# 02_MCU.net
KiCad netlist of a schematic drawn in Altium Designer
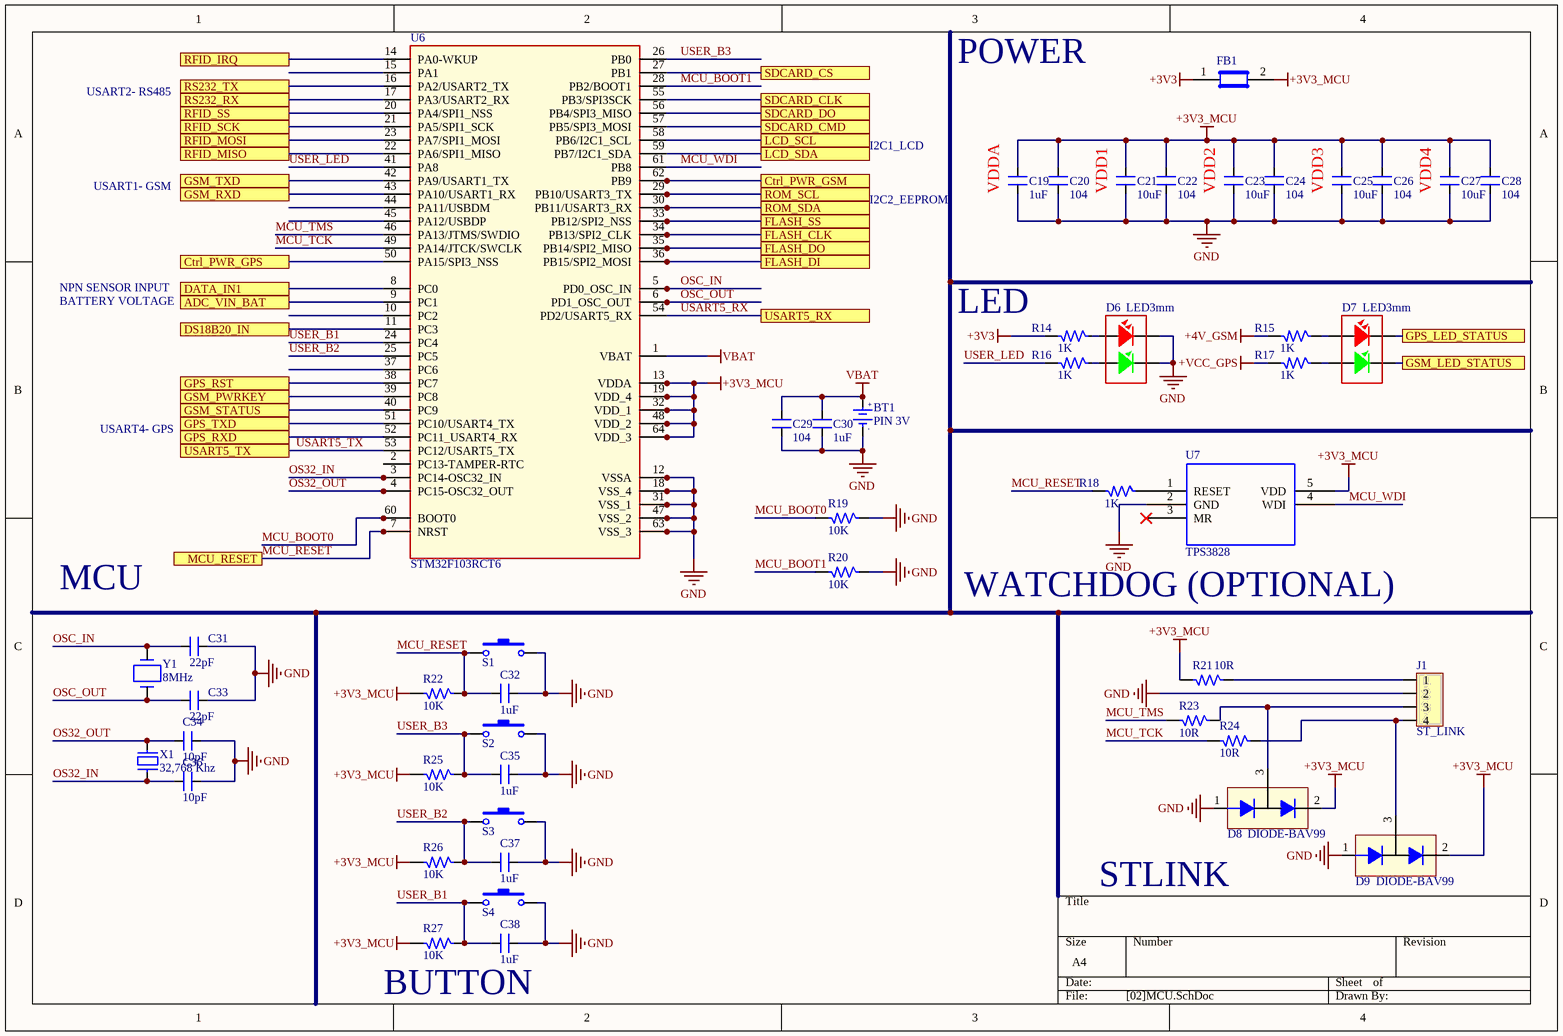
[diagram p0: [02]MCU.SchDoc]

(export (version "E")
  (design (tool "Eeschema 10.0.6"))
  (components
    (comp (ref "BT1")
      (value "PIN 3V")
      (footprint "My Library:CR1220 SMD")
      (description "Battery 3VDC")
      (libsource (lib "My Library") (part "PIN 3V"))
    )
    (comp (ref "C19")
      (value "1uF")
      (footprint "C0603 SMT")
      (description "Cap SMD")
      (libsource (lib "GPS_Traking_V1_1") (part "CM"))
    )
    (comp (ref "C20")
      (value "104")
      (footprint "C0603 SMT")
      (description "Cap SMD")
      (libsource (lib "GPS_Traking_V1_1") (part "CM"))
    )
    (comp (ref "C21")
      (value "10uF")
      (footprint "C0603 SMT")
      (description "Cap SMD")
      (libsource (lib "GPS_Traking_V1_1") (part "CM"))
    )
    (comp (ref "C22")
      (value "104")
      (footprint "C0603 SMT")
      (description "Cap SMD")
      (libsource (lib "GPS_Traking_V1_1") (part "CM"))
    )
    (comp (ref "C23")
      (value "10uF")
      (footprint "C0603 SMT")
      (description "Cap SMD")
      (libsource (lib "GPS_Traking_V1_1") (part "CM"))
    )
    (comp (ref "C24")
      (value "104")
      (footprint "C0603 SMT")
      (description "Cap SMD")
      (libsource (lib "GPS_Traking_V1_1") (part "CM"))
    )
    (comp (ref "C25")
      (value "10uF")
      (footprint "C0603 SMT")
      (description "Cap SMD")
      (libsource (lib "GPS_Traking_V1_1") (part "CM"))
    )
    (comp (ref "C26")
      (value "104")
      (footprint "C0603 SMT")
      (description "Cap SMD")
      (libsource (lib "GPS_Traking_V1_1") (part "CM"))
    )
    (comp (ref "C27")
      (value "10uF")
      (footprint "C0603 SMT")
      (description "Cap SMD")
      (libsource (lib "GPS_Traking_V1_1") (part "CM"))
    )
    (comp (ref "C28")
      (value "104")
      (footprint "C0603 SMT")
      (description "Cap SMD")
      (libsource (lib "GPS_Traking_V1_1") (part "CM"))
    )
    (comp (ref "C29")
      (value "104")
      (footprint "C0603 SMT")
      (description "Cap SMD")
      (libsource (lib "GPS_Traking_V1_1") (part "CM"))
    )
    (comp (ref "C30")
      (value "1uF")
      (footprint "C0603 SMT")
      (description "Cap SMD")
      (libsource (lib "GPS_Traking_V1_1") (part "CM"))
    )
    (comp (ref "C31")
      (value "22pF")
      (footprint "C0603 SMT")
      (description "Cap SMD")
      (libsource (lib "GPS_Traking_V1_1") (part "CM"))
    )
    (comp (ref "C32")
      (value "1uF")
      (footprint "C0603 SMT")
      (description "Cap SMD")
      (libsource (lib "GPS_Traking_V1_1") (part "CM"))
    )
    (comp (ref "C33")
      (value "22pF")
      (footprint "C0603 SMT")
      (description "Cap SMD")
      (libsource (lib "GPS_Traking_V1_1") (part "CM"))
    )
    (comp (ref "C34")
      (value "10pF")
      (footprint "C0603 SMT")
      (description "Cap SMD")
      (libsource (lib "GPS_Traking_V1_1") (part "CM"))
    )
    (comp (ref "C35")
      (value "1uF")
      (footprint "C0603 SMT")
      (description "Cap SMD")
      (libsource (lib "GPS_Traking_V1_1") (part "CM"))
    )
    (comp (ref "C36")
      (value "10pF")
      (footprint "C0603 SMT")
      (description "Cap SMD")
      (libsource (lib "GPS_Traking_V1_1") (part "CM"))
    )
    (comp (ref "C37")
      (value "1uF")
      (footprint "C0603 SMT")
      (description "Cap SMD")
      (libsource (lib "GPS_Traking_V1_1") (part "CM"))
    )
    (comp (ref "C38")
      (value "1uF")
      (footprint "C0603 SMT")
      (description "Cap SMD")
      (libsource (lib "GPS_Traking_V1_1") (part "CM"))
    )
    (comp (ref "D6")
      (value "LED3mm")
      (footprint "GPS_Traking_V1_1:LED 2 holder 3mm")
      (description "LED 2 holder RGB 3mm")
      (libsource (lib "GPS_Traking_V1_1") (part "LED2Holder_3mm"))
    )
    (comp (ref "D7")
      (value "LED3mm")
      (footprint "GPS_Traking_V1_1:LED 2 holder 3mm")
      (description "LED 2 holder RGB 3mm")
      (libsource (lib "GPS_Traking_V1_1") (part "LED2Holder_3mm"))
    )
    (comp (ref "D8")
      (value "DIODE-BAV99")
      (footprint "SOT23")
      (description "ZENER, SOT23,")
      (fields
        (field (name "MANUFACTURER") "ON Semiconductor / Fairchild")
        (field (name "MANUFACTURER PART NUMBER") "BAV99")
        (field (name ".CREATOR") "LeKhaLinh")
        (field (name ".CHECKPCB") "LeKhaLinh")
        (field (name ".CHECKSCH") "LeKhaLinh")
      )
      (libsource (lib "GPS_Traking_V1_1") (part "DIODE-BAV99"))
    )
    (comp (ref "D9")
      (value "DIODE-BAV99")
      (footprint "SOT23")
      (description "ZENER, SOT23,")
      (fields
        (field (name "MANUFACTURER") "ON Semiconductor / Fairchild")
        (field (name "MANUFACTURER PART NUMBER") "BAV99")
        (field (name ".CREATOR") "LeKhaLinh")
        (field (name ".CHECKPCB") "LeKhaLinh")
        (field (name ".CHECKSCH") "LeKhaLinh")
      )
      (libsource (lib "GPS_Traking_V1_1") (part "DIODE-BAV99"))
    )
    (comp (ref "FB1")
      (value "BLM21PG600SN1D")
      (footprint "RES-SMD-0805")
      (description "Ferrite Bead")
      (libsource (lib "khapham") (part "Ferrite Bead"))
    )
    (comp (ref "J1")
      (value "ST_LINK")
      (footprint "CON_4P")
      (description "Header IDC, 4 x 1 Pin Vertical 2.54mm Pitch (Non-Boxed, Male)")
      (fields
        (field (name "MANUFACTURER") "Würth Elektronik eiSos GmbH")
        (field (name "PARTNO") "613002143121")
        (field (name "CREATED BY") "Karrer Zheng")
      )
      (libsource (lib "My Library") (part "Header4"))
    )
    (comp (ref "R14")
      (value "1K")
      (footprint "RES-SMD-0805")
      (description "Resistor SMD")
      (libsource (lib "GPS_Traking_V1_1") (part "RM"))
    )
    (comp (ref "R15")
      (value "1K")
      (footprint "RES-SMD-0805")
      (description "Resistor SMD")
      (libsource (lib "GPS_Traking_V1_1") (part "RM"))
    )
    (comp (ref "R16")
      (value "1K")
      (footprint "RES-SMD-0805")
      (description "Resistor SMD")
      (libsource (lib "GPS_Traking_V1_1") (part "RM"))
    )
    (comp (ref "R17")
      (value "1K")
      (footprint "RES-SMD-0805")
      (description "Resistor SMD")
      (libsource (lib "GPS_Traking_V1_1") (part "RM"))
    )
    (comp (ref "R18")
      (value "1K")
      (footprint "RES-SMD-0603")
      (description "Resistor SMD")
      (libsource (lib "GPS_Traking_V1_1") (part "RM"))
    )
    (comp (ref "R19")
      (value "10K")
      (footprint "R0603 -SMT")
      (description "Resistor SMD")
      (libsource (lib "GPS_Traking_V1_1") (part "RM"))
    )
    (comp (ref "R20")
      (value "10K")
      (footprint "R0603 -SMT")
      (description "Resistor SMD")
      (libsource (lib "GPS_Traking_V1_1") (part "RM"))
    )
    (comp (ref "R21")
      (value "10R")
      (footprint "RES-SMD-0603")
      (description "Resistor SMD")
      (libsource (lib "GPS_Traking_V1_1") (part "RM"))
    )
    (comp (ref "R22")
      (value "10K")
      (footprint "R0603 -SMT")
      (description "Resistor SMD")
      (libsource (lib "GPS_Traking_V1_1") (part "RM"))
    )
    (comp (ref "R23")
      (value "10R")
      (footprint "RES-SMD-0603")
      (description "Resistor SMD")
      (libsource (lib "GPS_Traking_V1_1") (part "RM"))
    )
    (comp (ref "R24")
      (value "10R")
      (footprint "RES-SMD-0603")
      (description "Resistor SMD")
      (libsource (lib "GPS_Traking_V1_1") (part "RM"))
    )
    (comp (ref "R25")
      (value "10K")
      (footprint "R0603 -SMT")
      (description "Resistor SMD")
      (libsource (lib "GPS_Traking_V1_1") (part "RM"))
    )
    (comp (ref "R26")
      (value "10K")
      (footprint "R0603 -SMT")
      (description "Resistor SMD")
      (libsource (lib "GPS_Traking_V1_1") (part "RM"))
    )
    (comp (ref "R27")
      (value "10K")
      (footprint "R0603 -SMT")
      (description "Resistor SMD")
      (libsource (lib "GPS_Traking_V1_1") (part "RM"))
    )
    (comp (ref "S1")
      (value "SW-SMD")
      (footprint "SW-SMD")
      (description "Switch")
      (fields (field (name "PUBLISHER") "Altium Limited"))
      (libsource (lib "My Library") (part "SW-SMD"))
    )
    (comp (ref "S2")
      (value "SW-SMD")
      (footprint "BUTTON NGHIENG")
      (description "Switch")
      (fields (field (name "PUBLISHER") "Altium Limited"))
      (libsource (lib "My Library") (part "SW-SMD"))
    )
    (comp (ref "S3")
      (value "SW-SMD")
      (footprint "BUTTON NGHIENG")
      (description "Switch")
      (fields (field (name "PUBLISHER") "Altium Limited"))
      (libsource (lib "My Library") (part "SW-SMD"))
    )
    (comp (ref "S4")
      (value "SW-SMD")
      (footprint "BUTTON NGHIENG")
      (description "Switch")
      (fields (field (name "PUBLISHER") "Altium Limited"))
      (libsource (lib "My Library") (part "SW-SMD"))
    )
    (comp (ref "U6")
      (value "STM32F103RCT6")
      (footprint "LQFP-64")
      (description "MCU 32BIT 256KB FLASH 64LQFP")
      (libsource (lib "GPS_Traking_V1_1") (part "STM32F103RCT6"))
    )
    (comp (ref "U7")
      (value "TPS3828")
      (footprint "TPS3828")
      (libsource (lib "GPS_Traking_V1_1") (part "TPS3828"))
    )
    (comp (ref "X1")
      (value "32,768 Khz")
      (footprint "XT32kn")
      (description "Crystal 32,768kHz for timer real")
      (libsource (lib "GPS_Traking_V1_1") (part "XT32k"))
    )
    (comp (ref "Y1")
      (value "8MHz")
      (footprint "GPS_Traking_V1_1:ABM7_v1_1_BIG")
      (description "CRYSTAL 16MHZ 18PF SMD")
      (fields
        (field (name "MANUFACTURER") "Abracon LLC")
        (field (name "MANUFACTURER PART NUMBER") "ABM7-16.000MHZ-D2Y-T")
        (field (name ".CREATOR") "MM")
        (field (name ".CHECKED PCB") "RF")
        (field (name ".CHECKED SCH") "RF")
      )
      (libsource (lib "GPS_Traking_V1_1") (part "ABM7-16.000MHZ-D2Y-T"))
    )
  )
  (nets
    (net (code "1") (name "+3V3") (class "Default")
      (node (ref "FB1") (pin "1") (pinfunction "1_1") (pintype "passive"))
      (node (ref "R14") (pin "2") (pinfunction "2_2") (pintype "passive"))
    )
    (net (code "2") (name "+3V3_MCU") (class "Default")
      (node (ref "C19") (pin "2") (pinfunction "2_2") (pintype "passive"))
      (node (ref "C20") (pin "2") (pinfunction "2_2") (pintype "passive"))
      (node (ref "C21") (pin "2") (pinfunction "2_2") (pintype "passive"))
      (node (ref "C22") (pin "2") (pinfunction "2_2") (pintype "passive"))
      (node (ref "C23") (pin "2") (pinfunction "2_2") (pintype "passive"))
      (node (ref "C24") (pin "2") (pinfunction "2_2") (pintype "passive"))
      (node (ref "C25") (pin "2") (pinfunction "2_2") (pintype "passive"))
      (node (ref "C26") (pin "2") (pinfunction "2_2") (pintype "passive"))
      (node (ref "C27") (pin "2") (pinfunction "2_2") (pintype "passive"))
      (node (ref "C28") (pin "2") (pinfunction "2_2") (pintype "passive"))
      (node (ref "D8") (pin "2") (pinfunction "2_2") (pintype "passive"))
      (node (ref "D9") (pin "2") (pinfunction "2_2") (pintype "passive"))
      (node (ref "FB1") (pin "2") (pinfunction "2_2") (pintype "passive"))
      (node (ref "R21") (pin "2") (pinfunction "2_2") (pintype "passive"))
      (node (ref "R22") (pin "2") (pinfunction "2_2") (pintype "passive"))
      (node (ref "R25") (pin "2") (pinfunction "2_2") (pintype "passive"))
      (node (ref "R26") (pin "2") (pinfunction "2_2") (pintype "passive"))
      (node (ref "R27") (pin "2") (pinfunction "2_2") (pintype "passive"))
      (node (ref "U6") (pin "13") (pinfunction "VDDA_13") (pintype "passive"))
      (node (ref "U6") (pin "19") (pinfunction "VDD_4_19") (pintype "passive"))
      (node (ref "U6") (pin "32") (pinfunction "VDD_1_32") (pintype "passive"))
      (node (ref "U6") (pin "48") (pinfunction "VDD_2_48") (pintype "passive"))
      (node (ref "U6") (pin "64") (pinfunction "VDD_3_64") (pintype "passive"))
      (node (ref "U7") (pin "5") (pinfunction "VDD_5") (pintype "power_in"))
    )
    (net (code "3") (name "+4V_GSM") (class "Default")
      (node (ref "R15") (pin "2") (pinfunction "2_2") (pintype "passive"))
    )
    (net (code "4") (name "+VCC_GPS") (class "Default")
      (node (ref "R17") (pin "2") (pinfunction "2_2") (pintype "passive"))
    )
    (net (code "5") (name "/ADC_VIN_BAT") (class "Default")
      (node (ref "U6") (pin "9") (pinfunction "PC1_9") (pintype "passive"))
    )
    (net (code "6") (name "/Ctrl_PWR_GPS") (class "Default")
      (node (ref "U6") (pin "50") (pinfunction "PA15/SPI3_NSS_50") (pintype "passive"))
    )
    (net (code "7") (name "/Ctrl_PWR_GSM") (class "Default")
      (node (ref "U6") (pin "62") (pinfunction "PB9_62") (pintype "passive"))
    )
    (net (code "8") (name "/DATA_IN1") (class "Default")
      (node (ref "U6") (pin "8") (pinfunction "PC0_8") (pintype "passive"))
    )
    (net (code "9") (name "/DS18B20_IN") (class "Default")
      (node (ref "U6") (pin "11") (pinfunction "PC3_11") (pintype "passive"))
    )
    (net (code "10") (name "/FLASH_CLK") (class "Default")
      (node (ref "U6") (pin "34") (pinfunction "PB13/SPI2_CLK_34") (pintype "passive"))
    )
    (net (code "11") (name "/FLASH_DI") (class "Default")
      (node (ref "U6") (pin "36") (pinfunction "PB15/SPI2_MOSI_36") (pintype "passive"))
    )
    (net (code "12") (name "/FLASH_DO") (class "Default")
      (node (ref "U6") (pin "35") (pinfunction "PB14/SPI2_MISO_35") (pintype "passive"))
    )
    (net (code "13") (name "/FLASH_SS") (class "Default")
      (node (ref "U6") (pin "33") (pinfunction "PB12/SPI2_NSS_33") (pintype "passive"))
    )
    (net (code "14") (name "/GPS_LED_STATUS") (class "Default")
      (node (ref "D7") (pin "1") (pinfunction "1_1") (pintype "passive"))
    )
    (net (code "15") (name "/GPS_RST") (class "Default")
      (node (ref "U6") (pin "38") (pinfunction "PC7_38") (pintype "passive"))
    )
    (net (code "16") (name "/GPS_RXD") (class "Default")
      (node (ref "U6") (pin "52") (pinfunction "PC11_USART4_RX_52") (pintype "passive"))
    )
    (net (code "17") (name "/GPS_TXD") (class "Default")
      (node (ref "U6") (pin "51") (pinfunction "PC10/USART4_TX_51") (pintype "passive"))
    )
    (net (code "18") (name "/GSM_LED_STATUS") (class "Default")
      (node (ref "D7") (pin "3") (pinfunction "3_3") (pintype "passive"))
    )
    (net (code "19") (name "/GSM_PWRKEY") (class "Default")
      (node (ref "U6") (pin "39") (pinfunction "PC8_39") (pintype "passive"))
    )
    (net (code "20") (name "/GSM_RXD") (class "Default")
      (node (ref "U6") (pin "43") (pinfunction "PA10/USART1_RX_43") (pintype "passive"))
    )
    (net (code "21") (name "/GSM_STATUS") (class "Default")
      (node (ref "U6") (pin "40") (pinfunction "PC9_40") (pintype "passive"))
    )
    (net (code "22") (name "/GSM_TXD") (class "Default")
      (node (ref "U6") (pin "42") (pinfunction "PA9/USART1_TX_42") (pintype "passive"))
    )
    (net (code "23") (name "/LCD_SCL") (class "Default")
      (node (ref "U6") (pin "58") (pinfunction "PB6/I2C1_SCL_58") (pintype "passive"))
    )
    (net (code "24") (name "/LCD_SDA") (class "Default")
      (node (ref "U6") (pin "59") (pinfunction "PB7/I2C1_SDA_59") (pintype "passive"))
    )
    (net (code "25") (name "/MCU_BOOT0") (class "Default")
      (node (ref "R19") (pin "2") (pinfunction "2_2") (pintype "passive"))
      (node (ref "U6") (pin "60") (pinfunction "BOOT0_60") (pintype "passive"))
    )
    (net (code "26") (name "/MCU_BOOT1") (class "Default")
      (node (ref "R20") (pin "2") (pinfunction "2_2") (pintype "passive"))
      (node (ref "U6") (pin "28") (pinfunction "PB2/BOOT1_28") (pintype "passive"))
    )
    (net (code "27") (name "/MCU_RESET") (class "Default")
      (node (ref "C32") (pin "1") (pinfunction "1_1") (pintype "passive"))
      (node (ref "R18") (pin "2") (pinfunction "2_2") (pintype "passive"))
      (node (ref "R22") (pin "1") (pinfunction "1_1") (pintype "passive"))
      (node (ref "S1") (pin "1") (pinfunction "1_1") (pintype "passive"))
      (node (ref "U6") (pin "7") (pinfunction "NRST_7") (pintype "passive"))
    )
    (net (code "28") (name "/MCU_TCK") (class "Default")
      (node (ref "R24") (pin "2") (pinfunction "2_2") (pintype "passive"))
      (node (ref "U6") (pin "49") (pinfunction "PA14/JTCK/SWCLK_49") (pintype "passive"))
    )
    (net (code "29") (name "/MCU_TMS") (class "Default")
      (node (ref "R23") (pin "2") (pinfunction "2_2") (pintype "passive"))
      (node (ref "U6") (pin "46") (pinfunction "PA13/JTMS/SWDIO_46") (pintype "passive"))
    )
    (net (code "30") (name "/MCU_WDI") (class "Default")
      (node (ref "U6") (pin "61") (pinfunction "PB8_61") (pintype "passive"))
      (node (ref "U7") (pin "4") (pinfunction "WDI_4") (pintype "passive"))
    )
    (net (code "31") (name "/OS32_IN") (class "Default")
      (node (ref "C36") (pin "1") (pinfunction "1_1") (pintype "passive"))
      (node (ref "U6") (pin "3") (pinfunction "PC14-OSC32_IN_3") (pintype "passive"))
      (node (ref "X1") (pin "1") (pinfunction "1_1") (pintype "passive"))
    )
    (net (code "32") (name "/OS32_OUT") (class "Default")
      (node (ref "C34") (pin "1") (pinfunction "1_1") (pintype "passive"))
      (node (ref "U6") (pin "4") (pinfunction "PC15-OSC32_OUT_4") (pintype "passive"))
      (node (ref "X1") (pin "2") (pinfunction "2_2") (pintype "passive"))
    )
    (net (code "33") (name "/OSC_IN") (class "Default")
      (node (ref "C31") (pin "1") (pinfunction "1_1") (pintype "passive"))
      (node (ref "U6") (pin "5") (pinfunction "PD0_OSC_IN_5") (pintype "passive"))
      (node (ref "Y1") (pin "2") (pinfunction "2_2") (pintype "passive"))
    )
    (net (code "34") (name "/OSC_OUT") (class "Default")
      (node (ref "C33") (pin "1") (pinfunction "1_1") (pintype "passive"))
      (node (ref "U6") (pin "6") (pinfunction "PD1_OSC_OUT_6") (pintype "passive"))
      (node (ref "Y1") (pin "1") (pinfunction "1_1") (pintype "passive"))
    )
    (net (code "35") (name "/RFID_IRQ") (class "Default")
      (node (ref "U6") (pin "14") (pinfunction "PA0-WKUP_14") (pintype "passive"))
    )
    (net (code "36") (name "/RFID_MISO") (class "Default")
      (node (ref "U6") (pin "22") (pinfunction "PA6/SPI1_MISO_22") (pintype "passive"))
    )
    (net (code "37") (name "/RFID_MOSI") (class "Default")
      (node (ref "U6") (pin "23") (pinfunction "PA7/SPI1_MOSI_23") (pintype "passive"))
    )
    (net (code "38") (name "/RFID_SCK") (class "Default")
      (node (ref "U6") (pin "21") (pinfunction "PA5/SPI1_SCK_21") (pintype "passive"))
    )
    (net (code "39") (name "/RFID_SS") (class "Default")
      (node (ref "U6") (pin "20") (pinfunction "PA4/SPI1_NSS_20") (pintype "passive"))
    )
    (net (code "40") (name "/ROM_SCL") (class "Default")
      (node (ref "U6") (pin "29") (pinfunction "PB10/USART3_TX_29") (pintype "passive"))
    )
    (net (code "41") (name "/ROM_SDA") (class "Default")
      (node (ref "U6") (pin "30") (pinfunction "PB11/USART3_RX_30") (pintype "passive"))
    )
    (net (code "42") (name "/RS232_RX") (class "Default")
      (node (ref "U6") (pin "17") (pinfunction "PA3/USART2_RX_17") (pintype "passive"))
    )
    (net (code "43") (name "/RS232_TX") (class "Default")
      (node (ref "U6") (pin "16") (pinfunction "PA2/USART2_TX_16") (pintype "passive"))
    )
    (net (code "44") (name "/SDCARD_CLK") (class "Default")
      (node (ref "U6") (pin "55") (pinfunction "PB3/SPI3SCK_55") (pintype "passive"))
    )
    (net (code "45") (name "/SDCARD_CMD") (class "Default")
      (node (ref "U6") (pin "57") (pinfunction "PB5/SPI3_MOSI_57") (pintype "passive"))
    )
    (net (code "46") (name "/SDCARD_CS") (class "Default")
      (node (ref "U6") (pin "27") (pinfunction "PB1_27") (pintype "passive"))
    )
    (net (code "47") (name "/SDCARD_DO") (class "Default")
      (node (ref "U6") (pin "56") (pinfunction "PB4/SPI3_MISO_56") (pintype "passive"))
    )
    (net (code "48") (name "/USART5_RX") (class "Default")
      (node (ref "U6") (pin "54") (pinfunction "PD2/USART5_RX_54") (pintype "passive"))
    )
    (net (code "49") (name "/USART5_TX") (class "Default")
      (node (ref "U6") (pin "53") (pinfunction "PC12/USART5_TX_53") (pintype "passive"))
    )
    (net (code "50") (name "/USER_B1") (class "Default")
      (node (ref "C38") (pin "1") (pinfunction "1_1") (pintype "passive"))
      (node (ref "R27") (pin "1") (pinfunction "1_1") (pintype "passive"))
      (node (ref "S4") (pin "1") (pinfunction "1_1") (pintype "passive"))
      (node (ref "U6") (pin "24") (pinfunction "PC4_24") (pintype "passive"))
    )
    (net (code "51") (name "/USER_B2") (class "Default")
      (node (ref "C37") (pin "1") (pinfunction "1_1") (pintype "passive"))
      (node (ref "R26") (pin "1") (pinfunction "1_1") (pintype "passive"))
      (node (ref "S3") (pin "1") (pinfunction "1_1") (pintype "passive"))
      (node (ref "U6") (pin "25") (pinfunction "PC5_25") (pintype "passive"))
    )
    (net (code "52") (name "/USER_B3") (class "Default")
      (node (ref "C35") (pin "1") (pinfunction "1_1") (pintype "passive"))
      (node (ref "R25") (pin "1") (pinfunction "1_1") (pintype "passive"))
      (node (ref "S2") (pin "1") (pinfunction "1_1") (pintype "passive"))
      (node (ref "U6") (pin "26") (pinfunction "PB0_26") (pintype "passive"))
    )
    (net (code "53") (name "/USER_LED") (class "Default")
      (node (ref "R16") (pin "2") (pinfunction "2_2") (pintype "passive"))
      (node (ref "U6") (pin "41") (pinfunction "PA8_41") (pintype "passive"))
    )
    (net (code "54") (name "GND") (class "Default")
      (node (ref "BT1") (pin "2") (pinfunction "GND_2") (pintype "passive"))
      (node (ref "C19") (pin "1") (pinfunction "1_1") (pintype "passive"))
      (node (ref "C20") (pin "1") (pinfunction "1_1") (pintype "passive"))
      (node (ref "C21") (pin "1") (pinfunction "1_1") (pintype "passive"))
      (node (ref "C22") (pin "1") (pinfunction "1_1") (pintype "passive"))
      (node (ref "C23") (pin "1") (pinfunction "1_1") (pintype "passive"))
      (node (ref "C24") (pin "1") (pinfunction "1_1") (pintype "passive"))
      (node (ref "C25") (pin "1") (pinfunction "1_1") (pintype "passive"))
      (node (ref "C26") (pin "1") (pinfunction "1_1") (pintype "passive"))
      (node (ref "C27") (pin "1") (pinfunction "1_1") (pintype "passive"))
      (node (ref "C28") (pin "1") (pinfunction "1_1") (pintype "passive"))
      (node (ref "C29") (pin "1") (pinfunction "1_1") (pintype "passive"))
      (node (ref "C30") (pin "1") (pinfunction "1_1") (pintype "passive"))
      (node (ref "C31") (pin "2") (pinfunction "2_2") (pintype "passive"))
      (node (ref "C32") (pin "2") (pinfunction "2_2") (pintype "passive"))
      (node (ref "C33") (pin "2") (pinfunction "2_2") (pintype "passive"))
      (node (ref "C34") (pin "2") (pinfunction "2_2") (pintype "passive"))
      (node (ref "C35") (pin "2") (pinfunction "2_2") (pintype "passive"))
      (node (ref "C36") (pin "2") (pinfunction "2_2") (pintype "passive"))
      (node (ref "C37") (pin "2") (pinfunction "2_2") (pintype "passive"))
      (node (ref "C38") (pin "2") (pinfunction "2_2") (pintype "passive"))
      (node (ref "D6") (pin "1") (pinfunction "1_1") (pintype "passive"))
      (node (ref "D6") (pin "3") (pinfunction "3_3") (pintype "passive"))
      (node (ref "D8") (pin "1") (pinfunction "1_1") (pintype "passive"))
      (node (ref "D9") (pin "1") (pinfunction "1_1") (pintype "passive"))
      (node (ref "J1") (pin "2") (pinfunction "2_2") (pintype "passive"))
      (node (ref "R19") (pin "1") (pinfunction "1_1") (pintype "passive"))
      (node (ref "R20") (pin "1") (pinfunction "1_1") (pintype "passive"))
      (node (ref "S1") (pin "2") (pinfunction "2_2") (pintype "passive"))
      (node (ref "S2") (pin "2") (pinfunction "2_2") (pintype "passive"))
      (node (ref "S3") (pin "2") (pinfunction "2_2") (pintype "passive"))
      (node (ref "S4") (pin "2") (pinfunction "2_2") (pintype "passive"))
      (node (ref "U6") (pin "12") (pinfunction "VSSA_12") (pintype "passive"))
      (node (ref "U6") (pin "18") (pinfunction "VSS_4_18") (pintype "passive"))
      (node (ref "U6") (pin "31") (pinfunction "VSS_1_31") (pintype "passive"))
      (node (ref "U6") (pin "47") (pinfunction "VSS_2_47") (pintype "passive"))
      (node (ref "U6") (pin "63") (pinfunction "VSS_3_63") (pintype "passive"))
      (node (ref "U7") (pin "2") (pinfunction "GND_2") (pintype "power_in"))
    )
    (net (code "55") (name "Net-(D6-Pad2)") (class "Default")
      (node (ref "D6") (pin "2") (pinfunction "2_2") (pintype "passive"))
      (node (ref "R14") (pin "1") (pinfunction "1_1") (pintype "passive"))
    )
    (net (code "56") (name "Net-(D6-Pad4)") (class "Default")
      (node (ref "D6") (pin "4") (pinfunction "4_4") (pintype "passive"))
      (node (ref "R16") (pin "1") (pinfunction "1_1") (pintype "passive"))
    )
    (net (code "57") (name "Net-(D7-Pad2)") (class "Default")
      (node (ref "D7") (pin "2") (pinfunction "2_2") (pintype "passive"))
      (node (ref "R15") (pin "1") (pinfunction "1_1") (pintype "passive"))
    )
    (net (code "58") (name "Net-(D7-Pad4)") (class "Default")
      (node (ref "D7") (pin "4") (pinfunction "4_4") (pintype "passive"))
      (node (ref "R17") (pin "1") (pinfunction "1_1") (pintype "passive"))
    )
    (net (code "59") (name "Net-(D8-Pad3)") (class "Default")
      (node (ref "D8") (pin "3") (pinfunction "3_3") (pintype "passive"))
      (node (ref "J1") (pin "3") (pinfunction "3_3") (pintype "passive"))
      (node (ref "R23") (pin "1") (pinfunction "1_1") (pintype "passive"))
    )
    (net (code "60") (name "Net-(D9-Pad3)") (class "Default")
      (node (ref "D9") (pin "3") (pinfunction "3_3") (pintype "passive"))
      (node (ref "J1") (pin "4") (pinfunction "4_4") (pintype "passive"))
      (node (ref "R24") (pin "1") (pinfunction "1_1") (pintype "passive"))
    )
    (net (code "61") (name "Net-(J1-Pad1)") (class "Default")
      (node (ref "J1") (pin "1") (pinfunction "1_1") (pintype "passive"))
      (node (ref "R21") (pin "1") (pinfunction "1_1") (pintype "passive"))
    )
    (net (code "62") (name "Net-(U7-RESET)") (class "Default")
      (node (ref "R18") (pin "1") (pinfunction "1_1") (pintype "passive"))
      (node (ref "U7") (pin "1") (pinfunction "RESET_1") (pintype "passive"))
    )
    (net (code "63") (name "VBAT") (class "Default")
      (node (ref "BT1") (pin "1") (pinfunction "+3V_1") (pintype "passive"))
      (node (ref "C29") (pin "2") (pinfunction "2_2") (pintype "passive"))
      (node (ref "C30") (pin "2") (pinfunction "2_2") (pintype "passive"))
      (node (ref "U6") (pin "1") (pinfunction "VBAT_1") (pintype "passive"))
    )
    (net (code "64") (name "unconnected-(U6-PA1-Pad15)") (class "Default")
      (node (ref "U6") (pin "15") (pinfunction "PA1_15") (pintype "passive"))
    )
    (net (code "65") (name "unconnected-(U6-PA11{slash}USBDM-Pad44)") (class "Default")
      (node (ref "U6") (pin "44") (pinfunction "PA11/USBDM_44") (pintype "passive"))
    )
    (net (code "66") (name "unconnected-(U6-PA12{slash}USBDP-Pad45)") (class "Default")
      (node (ref "U6") (pin "45") (pinfunction "PA12/USBDP_45") (pintype "passive"))
    )
    (net (code "67") (name "unconnected-(U6-PC2-Pad10)") (class "Default")
      (node (ref "U6") (pin "10") (pinfunction "PC2_10") (pintype "passive"))
    )
    (net (code "68") (name "unconnected-(U6-PC6-Pad37)") (class "Default")
      (node (ref "U6") (pin "37") (pinfunction "PC6_37") (pintype "passive"))
    )
    (net (code "69") (name "unconnected-(U6-PC13-TAMPER-RTC-Pad2)") (class "Default")
      (node (ref "U6") (pin "2") (pinfunction "PC13-TAMPER-RTC_2") (pintype "passive"))
    )
    (net (code "70") (name "unconnected-(U7-MR-Pad3)") (class "Default")
      (node (ref "U7") (pin "3") (pinfunction "MR_3") (pintype "passive+no_connect"))
    )
  )
)
